# Addon-LAN-WLAN-without-MAPLE-V01-001.net
KiCad netlist of a schematic drawn in EAGLE
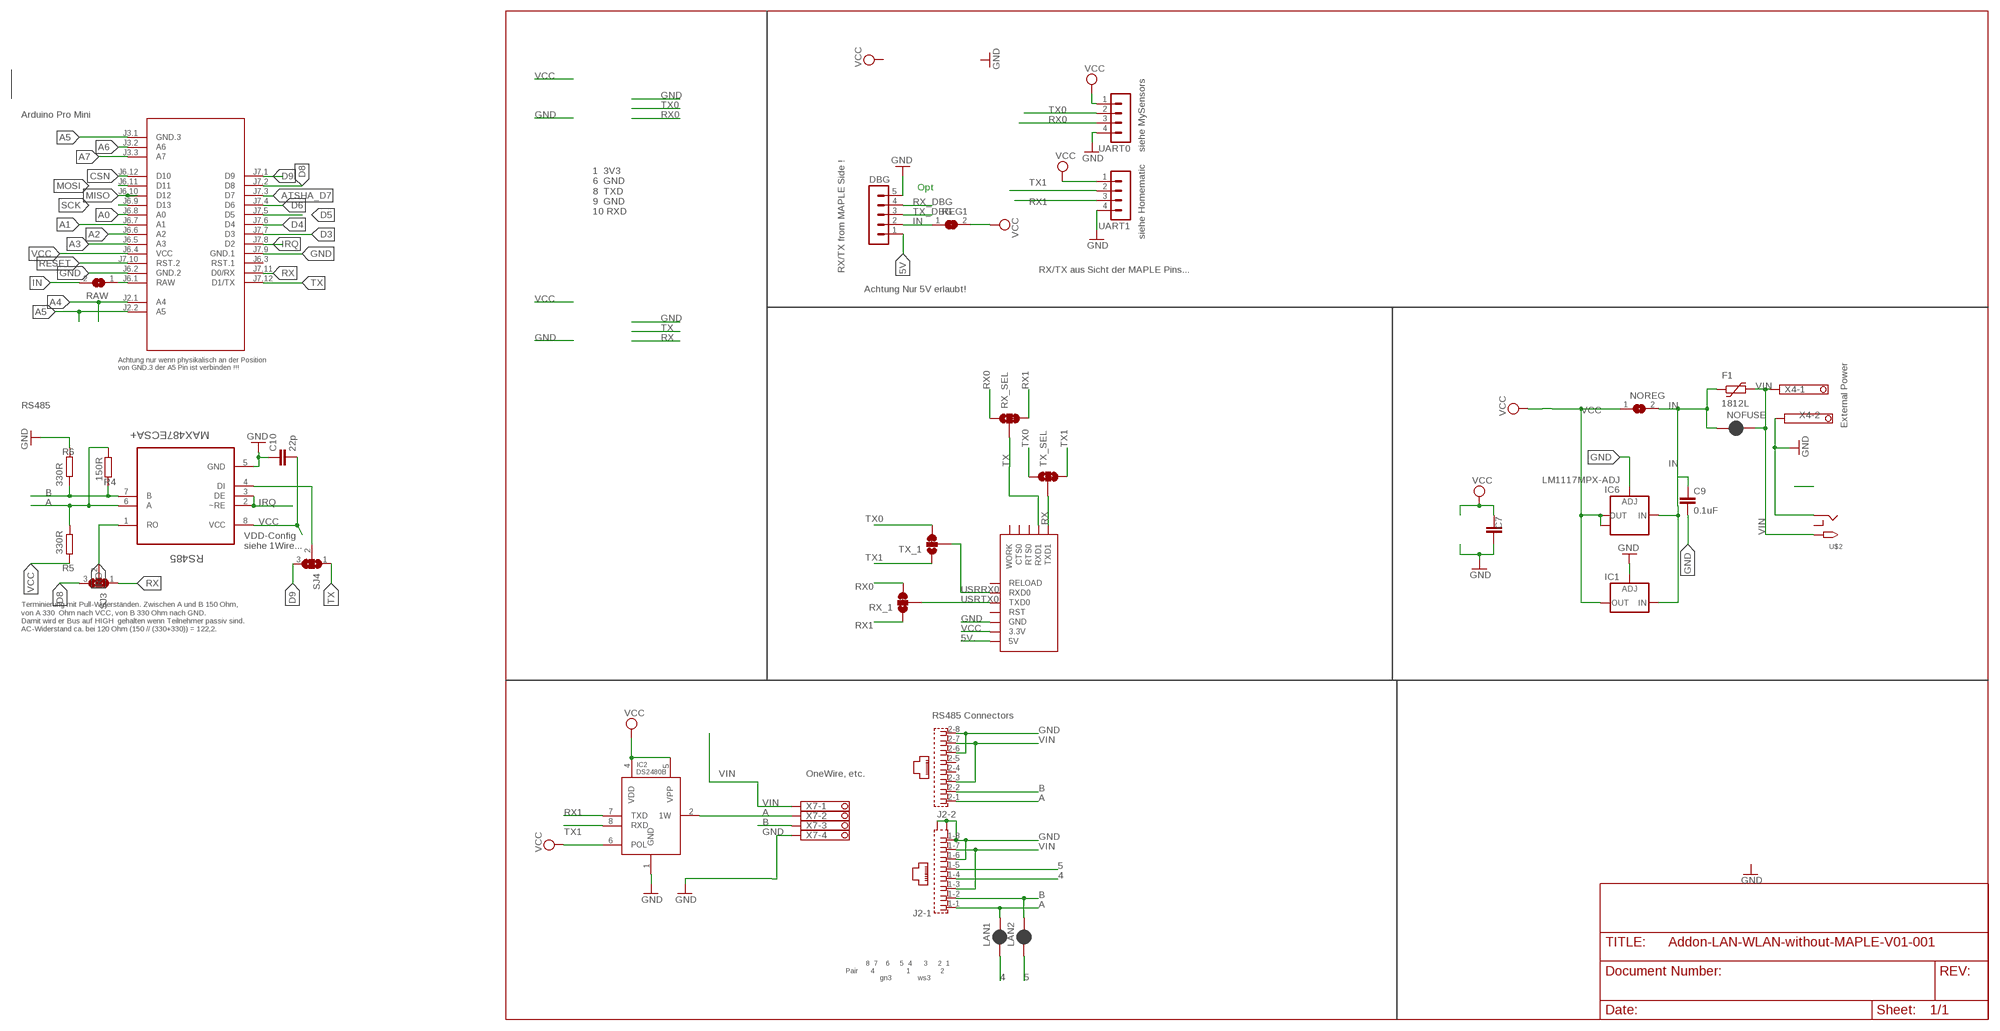
[diagram p0: schematic, sheet 1]

(export (version "E")
  (design (tool "Eeschema 10.0.6"))
  (components
    (comp (ref "C7")
      (value "C-EUC1812")
      (footprint "eagle-import:C1812")
      (libsource (lib "eagle-import") (part "rcl_334_C-EUC1812"))
    )
    (comp (ref "C9")
      (value "0.1uF")
      (footprint "eagle-import:C1206")
      (libsource (lib "eagle-import") (part "rcl_334_C-EUC1206"))
    )
    (comp (ref "C10")
      (value "22p")
      (footprint "eagle-import:C0805")
      (libsource (lib "eagle-import") (part "C-EUC0805"))
    )
    (comp (ref "DBG")
      (value "MA05-1")
      (footprint "eagle-import:MA05-1")
      (libsource (lib "eagle-import") (part "MA05-1"))
    )
    (comp (ref "F1")
      (value "1812L")
      (footprint "eagle-import:1812L")
      (libsource (lib "eagle-import") (part "1812L"))
    )
    (comp (ref "IC1")
      (value "LD117ADT50TR")
      (footprint "eagle-import:DPACK")
      (libsource (lib "eagle-import") (part "LD117A?DT50TR"))
    )
    (comp (ref "IC2")
      (value "DS2480B")
      (footprint "eagle-import:SO08")
      (libsource (lib "eagle-import") (part "DS2480B"))
    )
    (comp (ref "IC6")
      (value "LM1117MPX-ADJ")
      (footprint "eagle-import:SOT223")
      (libsource (lib "eagle-import") (part "LM1117MPX-ADJ"))
    )
    (comp (ref "J2")
      (value "RJ45_2X_S")
      (footprint "eagle-import:RJ45_2X_S")
      (libsource (lib "eagle-import") (part "RJ45_2X_S"))
    )
    (comp (ref "LAN1")
      (value "JUMPER-SMT_2_NC_PASTE_SILK")
      (footprint "eagle-import:SMT-JUMPER_2_NC_PASTE_SILK")
      (libsource (lib "eagle-import") (part "JUMPER-SMT_2_NC_PASTE_SILK"))
    )
    (comp (ref "LAN2")
      (value "JUMPER-SMT_2_NC_PASTE_SILK")
      (footprint "eagle-import:SMT-JUMPER_2_NC_PASTE_SILK")
      (libsource (lib "eagle-import") (part "JUMPER-SMT_2_NC_PASTE_SILK"))
    )
    (comp (ref "M1")
      (value "ARDUINO-PRO-MINI-3.3V#NP")
      (footprint "eagle-import:ARDUINO-PRO-MINI#NP")
      (libsource (lib "eagle-import") (part "ARDUINO-PRO-MINI-#NP3.3V"))
    )
    (comp (ref "NOFUSE")
      (value "JUMPER-SMT_2_NC_PASTE_NO-SILK")
      (footprint "eagle-import:SMT-JUMPER_2_NC_PASTE_NO-SILK")
      (libsource (lib "eagle-import") (part "JUMPER-SMT_2_NC_PASTE_NO-SILK"))
    )
    (comp (ref "NOREG")
      (value "SJ")
      (footprint "eagle-import:SJ")
      (libsource (lib "eagle-import") (part "jumper_252_SJ"))
    )
    (comp (ref "R4")
      (value "150R")
      (footprint "eagle-import:R0805")
      (libsource (lib "eagle-import") (part "R-EU_R0805"))
    )
    (comp (ref "R5")
      (value "330R")
      (footprint "eagle-import:R0805")
      (libsource (lib "eagle-import") (part "R-EU_R0805"))
    )
    (comp (ref "R6")
      (value "330R")
      (footprint "eagle-import:R0805")
      (libsource (lib "eagle-import") (part "R-EU_R0805"))
    )
    (comp (ref "RAW") (value "SJ") (footprint "eagle-import:SJ") (libsource (lib "eagle-import") (part "SJ")))
    (comp (ref "REG1")
      (value "SJ")
      (footprint "eagle-import:SJ")
      (libsource (lib "eagle-import") (part "jumper_252_SJ"))
    )
    (comp (ref "RS485")
      (value "MAX487ECSA+")
      (footprint "eagle-import:SOIC127P600X175-8N")
      (libsource (lib "eagle-import") (part "MAX487ECSA+"))
    )
    (comp (ref "RX_1")
      (value "JUMPER-SMT_3_1-NC_TRACE_SILK")
      (footprint "eagle-import:SMT-JUMPER_3_1-NC_TRACE_SILK")
      (libsource (lib "eagle-import") (part "JUMPER-SMT_3_1-NC_TRACE_SILK"))
    )
    (comp (ref "RX_SEL")
      (value "JUMPER-SMT_3_1-NC_TRACE_SILK")
      (footprint "eagle-import:SMT-JUMPER_3_1-NC_TRACE_SILK")
      (libsource (lib "eagle-import") (part "JUMPER-SMT_3_1-NC_TRACE_SILK"))
    )
    (comp (ref "SJ3")
      (value "SJ2W")
      (footprint "eagle-import:SJ_2")
      (libsource (lib "eagle-import") (part "SJ2W"))
    )
    (comp (ref "SJ4")
      (value "SJ2W")
      (footprint "eagle-import:SJ_2")
      (libsource (lib "eagle-import") (part "SJ2W"))
    )
    (comp (ref "TX_1")
      (value "JUMPER-SMT_3_1-NC_TRACE_SILK")
      (footprint "eagle-import:SMT-JUMPER_3_1-NC_TRACE_SILK")
      (libsource (lib "eagle-import") (part "JUMPER-SMT_3_1-NC_TRACE_SILK"))
    )
    (comp (ref "TX_SEL")
      (value "JUMPER-SMT_3_1-NC_TRACE_SILK")
      (footprint "eagle-import:SMT-JUMPER_3_1-NC_TRACE_SILK")
      (libsource (lib "eagle-import") (part "JUMPER-SMT_3_1-NC_TRACE_SILK"))
    )
    (comp (ref "U$2")
      (value "2.1MMJACKTHM")
      (footprint "eagle-import:PJ-102A")
      (libsource (lib "eagle-import") (part "2.1MMJACKTHM"))
    )
    (comp (ref "U$5")
      (value "USR-TCP232-E2")
      (footprint "eagle-import:USR-TCP232-E2")
      (libsource (lib "eagle-import") (part "USR-TCP232-E2"))
    )
    (comp (ref "UART0")
      (value "MA04-1")
      (footprint "eagle-import:MA04-1")
      (libsource (lib "eagle-import") (part "MA04-1"))
    )
    (comp (ref "UART1")
      (value "MA04-1")
      (footprint "eagle-import:MA04-1")
      (libsource (lib "eagle-import") (part "MA04-1"))
    )
    (comp (ref "X4")
      (value "1751248")
      (footprint "eagle-import:1751248")
      (libsource (lib "eagle-import") (part "1751248"))
    )
    (comp (ref "X7")
      (value "1751264")
      (footprint "eagle-import:1751264")
      (libsource (lib "eagle-import") (part "1751264"))
    )
  )
  (nets
    (net (code "1") (name "/4") (class "Default")
      (node (ref "J2") (pin "1-4") (pinfunction "4_1-4") (pintype "passive"))
      (node (ref "LAN1") (pin "1") (pinfunction "1_1") (pintype "passive"))
    )
    (net (code "2") (name "/5") (class "Default")
      (node (ref "J2") (pin "1-5") (pinfunction "5_1-5") (pintype "passive"))
      (node (ref "LAN2") (pin "1") (pinfunction "1_1") (pintype "passive"))
    )
    (net (code "3") (name "/5V.") (class "Default")
      (node (ref "U$5") (pin "5V") (pinfunction "5V_5V") (pintype "bidirectional"))
    )
    (net (code "4") (name "/A") (class "Default")
      (node (ref "IC2") (pin "2") (pinfunction "1W_2") (pintype "open_collector"))
      (node (ref "J2") (pin "1-1") (pinfunction "1_1-1") (pintype "passive"))
      (node (ref "J2") (pin "2-1") (pinfunction "1_2-1") (pintype "passive"))
      (node (ref "LAN1") (pin "2") (pinfunction "2_2") (pintype "passive"))
      (node (ref "R4") (pin "1") (pinfunction "1_1") (pintype "passive"))
      (node (ref "R5") (pin "2") (pinfunction "2_2") (pintype "passive"))
      (node (ref "RS485") (pin "6") (pinfunction "A_6") (pintype "bidirectional"))
      (node (ref "X7") (pin "2") (pinfunction "K_2") (pintype "passive"))
    )
    (net (code "5") (name "/B") (class "Default")
      (node (ref "J2") (pin "1-2") (pinfunction "2_1-2") (pintype "passive"))
      (node (ref "J2") (pin "2-2") (pinfunction "2_2-2") (pintype "passive"))
      (node (ref "LAN2") (pin "2") (pinfunction "2_2") (pintype "passive"))
      (node (ref "R4") (pin "2") (pinfunction "2_2") (pintype "passive"))
      (node (ref "R6") (pin "1") (pinfunction "1_1") (pintype "passive"))
      (node (ref "RS485") (pin "7") (pinfunction "B_7") (pintype "bidirectional"))
      (node (ref "X7") (pin "3") (pinfunction "K_3") (pintype "passive"))
    )
    (net (code "6") (name "/RX0") (class "Default")
      (node (ref "RX_1") (pin "3") (pinfunction "3_3") (pintype "passive"))
      (node (ref "RX_SEL") (pin "1") (pinfunction "1_1") (pintype "passive"))
      (node (ref "UART0") (pin "3") (pinfunction "3_3") (pintype "passive"))
    )
    (net (code "7") (name "/RX1") (class "Default")
      (node (ref "IC2") (pin "7") (pinfunction "TXD_7") (pintype "input"))
      (node (ref "RX_1") (pin "1") (pinfunction "1_1") (pintype "passive"))
      (node (ref "RX_SEL") (pin "3") (pinfunction "3_3") (pintype "passive"))
      (node (ref "UART1") (pin "3") (pinfunction "3_3") (pintype "passive"))
    )
    (net (code "8") (name "/RX_DBG") (class "Default")
      (node (ref "DBG") (pin "4") (pinfunction "4_4") (pintype "passive"))
    )
    (net (code "9") (name "/TX0") (class "Default")
      (node (ref "TX_1") (pin "3") (pinfunction "3_3") (pintype "passive"))
      (node (ref "TX_SEL") (pin "1") (pinfunction "1_1") (pintype "passive"))
      (node (ref "UART0") (pin "2") (pinfunction "2_2") (pintype "passive"))
    )
    (net (code "10") (name "/TX1") (class "Default")
      (node (ref "IC2") (pin "8") (pinfunction "RXD_8") (pintype "output"))
      (node (ref "TX_1") (pin "1") (pinfunction "1_1") (pintype "passive"))
      (node (ref "TX_SEL") (pin "3") (pinfunction "3_3") (pintype "passive"))
      (node (ref "UART1") (pin "2") (pinfunction "2_2") (pintype "passive"))
    )
    (net (code "11") (name "/TX_DBG") (class "Default")
      (node (ref "DBG") (pin "3") (pinfunction "3_3") (pintype "passive"))
    )
    (net (code "12") (name "/USRRX0") (class "Default")
      (node (ref "TX_1") (pin "2") (pinfunction "2_2") (pintype "passive"))
      (node (ref "U$5") (pin "RXD0") (pinfunction "RXD0_RXD0") (pintype "input"))
    )
    (net (code "13") (name "/USRTX0") (class "Default")
      (node (ref "RX_1") (pin "2") (pinfunction "2_2") (pintype "passive"))
      (node (ref "U$5") (pin "TXD0") (pinfunction "TXD0_TXD0") (pintype "output"))
    )
    (net (code "14") (name "/VIN") (class "Default")
      (node (ref "F1") (pin "P$2") (pinfunction "2_P$2") (pintype "passive"))
      (node (ref "J2") (pin "1-3") (pinfunction "3_1-3") (pintype "passive"))
      (node (ref "J2") (pin "1-7") (pinfunction "7_1-7") (pintype "passive"))
      (node (ref "J2") (pin "2-3") (pinfunction "3_2-3") (pintype "passive"))
      (node (ref "J2") (pin "2-7") (pinfunction "7_2-7") (pintype "passive"))
      (node (ref "NOFUSE") (pin "2") (pinfunction "2_2") (pintype "passive"))
      (node (ref "U$2") (pin "TIP") (pinfunction "TIP_TIP") (pintype "bidirectional"))
      (node (ref "X4") (pin "1") (pinfunction "K_1") (pintype "passive"))
      (node (ref "X7") (pin "1") (pinfunction "K_1") (pintype "passive"))
    )
    (net (code "15") (name "5V") (class "Default")
      (node (ref "DBG") (pin "1") (pinfunction "1_1") (pintype "passive"))
    )
    (net (code "16") (name "A0") (class "Default")
      (node (ref "M1") (pin "J6.8") (pinfunction "A0_J6.8") (pintype "bidirectional"))
    )
    (net (code "17") (name "A1") (class "Default")
      (node (ref "M1") (pin "J6.7") (pinfunction "A1_J6.7") (pintype "bidirectional"))
    )
    (net (code "18") (name "A2") (class "Default")
      (node (ref "M1") (pin "J6.6") (pinfunction "A2_J6.6") (pintype "bidirectional"))
    )
    (net (code "19") (name "A3") (class "Default")
      (node (ref "M1") (pin "J6.5") (pinfunction "A3_J6.5") (pintype "bidirectional"))
    )
    (net (code "20") (name "A4") (class "Default")
      (node (ref "M1") (pin "J2.1") (pinfunction "A4_J2.1") (pintype "bidirectional"))
    )
    (net (code "21") (name "A5") (class "Default")
      (node (ref "M1") (pin "J2.2") (pinfunction "A5_J2.2") (pintype "bidirectional"))
      (node (ref "M1") (pin "J3.1") (pinfunction "GND.3_J3.1") (pintype "bidirectional"))
    )
    (net (code "22") (name "A6") (class "Default")
      (node (ref "M1") (pin "J3.2") (pinfunction "A6_J3.2") (pintype "bidirectional"))
    )
    (net (code "23") (name "A7") (class "Default")
      (node (ref "M1") (pin "J3.3") (pinfunction "A7_J3.3") (pintype "bidirectional"))
    )
    (net (code "24") (name "ATSHA_D7") (class "Default")
      (node (ref "M1") (pin "J7.3") (pinfunction "D7_J7.3") (pintype "bidirectional"))
    )
    (net (code "25") (name "CSN") (class "Default")
      (node (ref "M1") (pin "J6.12") (pinfunction "D10_J6.12") (pintype "bidirectional"))
    )
    (net (code "26") (name "D3") (class "Default")
      (node (ref "M1") (pin "J7.7") (pinfunction "D3_J7.7") (pintype "bidirectional"))
    )
    (net (code "27") (name "D4") (class "Default")
      (node (ref "M1") (pin "J7.6") (pinfunction "D4_J7.6") (pintype "bidirectional"))
    )
    (net (code "28") (name "D5") (class "Default")
      (node (ref "M1") (pin "J7.5") (pinfunction "D5_J7.5") (pintype "bidirectional"))
    )
    (net (code "29") (name "D6") (class "Default")
      (node (ref "M1") (pin "J7.4") (pinfunction "D6_J7.4") (pintype "bidirectional"))
    )
    (net (code "30") (name "D8") (class "Default")
      (node (ref "M1") (pin "J7.2") (pinfunction "D8_J7.2") (pintype "bidirectional"))
      (node (ref "SJ3") (pin "3") (pinfunction "3_3") (pintype "passive"))
    )
    (net (code "31") (name "D9") (class "Default")
      (node (ref "M1") (pin "J7.1") (pinfunction "D9_J7.1") (pintype "bidirectional"))
      (node (ref "SJ4") (pin "3") (pinfunction "3_3") (pintype "passive"))
    )
    (net (code "32") (name "GND") (class "Default")
      (node (ref "C10") (pin "1") (pinfunction "1_1") (pintype "passive"))
      (node (ref "C7") (pin "1") (pinfunction "1_1") (pintype "passive"))
      (node (ref "C9") (pin "2") (pinfunction "2_2") (pintype "passive"))
      (node (ref "DBG") (pin "5") (pinfunction "5_5") (pintype "passive"))
      (node (ref "IC1") (pin "1") (pinfunction "ADJ_1") (pintype "input"))
      (node (ref "IC2") (pin "1") (pinfunction "GND_1") (pintype "power_in"))
      (node (ref "IC6") (pin "1") (pinfunction "ADJ_1") (pintype "input"))
      (node (ref "J2") (pin "1-6") (pinfunction "6_1-6") (pintype "passive"))
      (node (ref "J2") (pin "1-8") (pinfunction "8_1-8") (pintype "passive"))
      (node (ref "J2") (pin "2-6") (pinfunction "6_2-6") (pintype "passive"))
      (node (ref "J2") (pin "2-8") (pinfunction "8_2-8") (pintype "passive"))
      (node (ref "J2") (pin "G1") (pinfunction "S2_G1") (pintype "passive"))
      (node (ref "J2") (pin "G3") (pinfunction "S1_G3") (pintype "passive"))
      (node (ref "M1") (pin "J6.2") (pinfunction "GND.2_J6.2") (pintype "power_in"))
      (node (ref "M1") (pin "J7.9") (pinfunction "GND.1_J7.9") (pintype "power_in"))
      (node (ref "R6") (pin "2") (pinfunction "2_2") (pintype "passive"))
      (node (ref "RS485") (pin "5") (pinfunction "GND_5") (pintype "passive"))
      (node (ref "U$2") (pin "RING") (pinfunction "RING_RING") (pintype "bidirectional"))
      (node (ref "U$5") (pin "GND") (pinfunction "GND_GND") (pintype "bidirectional"))
      (node (ref "UART0") (pin "4") (pinfunction "4_4") (pintype "passive"))
      (node (ref "UART1") (pin "4") (pinfunction "4_4") (pintype "passive"))
      (node (ref "X4") (pin "2") (pinfunction "K_2") (pintype "passive"))
      (node (ref "X7") (pin "4") (pinfunction "K_4") (pintype "passive"))
    )
    (net (code "33") (name "IN") (class "Default")
      (node (ref "C9") (pin "1") (pinfunction "1_1") (pintype "passive"))
      (node (ref "DBG") (pin "2") (pinfunction "2_2") (pintype "passive"))
      (node (ref "F1") (pin "P$1") (pinfunction "1_P$1") (pintype "passive"))
      (node (ref "IC1") (pin "3") (pinfunction "IN_3") (pintype "input"))
      (node (ref "IC6") (pin "3") (pinfunction "IN_3") (pintype "input"))
      (node (ref "NOFUSE") (pin "1") (pinfunction "1_1") (pintype "passive"))
      (node (ref "NOREG") (pin "2") (pinfunction "2_2") (pintype "passive"))
      (node (ref "RAW") (pin "2") (pinfunction "2_2") (pintype "passive"))
      (node (ref "REG1") (pin "1") (pinfunction "1_1") (pintype "passive"))
    )
    (net (code "34") (name "IRQ") (class "Default")
      (node (ref "M1") (pin "J7.8") (pinfunction "D2_J7.8") (pintype "bidirectional"))
      (node (ref "RS485") (pin "2") (pinfunction "~{RE}_2") (pintype "input"))
      (node (ref "RS485") (pin "3") (pinfunction "DE_3") (pintype "input"))
    )
    (net (code "35") (name "MISO") (class "Default")
      (node (ref "M1") (pin "J6.10") (pinfunction "D12_J6.10") (pintype "bidirectional"))
    )
    (net (code "36") (name "MOSI") (class "Default")
      (node (ref "M1") (pin "J6.11") (pinfunction "D11_J6.11") (pintype "bidirectional"))
    )
    (net (code "37") (name "Net-(M1-RAW)") (class "Default")
      (node (ref "M1") (pin "J6.1") (pinfunction "RAW_J6.1") (pintype "power_in"))
      (node (ref "RAW") (pin "1") (pinfunction "1_1") (pintype "passive"))
    )
    (net (code "38") (name "Net-(RS485-DI)") (class "Default")
      (node (ref "RS485") (pin "4") (pinfunction "DI_4") (pintype "input"))
      (node (ref "SJ4") (pin "2") (pinfunction "2_2") (pintype "passive"))
    )
    (net (code "39") (name "RESET") (class "Default")
      (node (ref "M1") (pin "J7.10") (pinfunction "RST.2_J7.10") (pintype "bidirectional"))
    )
    (net (code "40") (name "RO") (class "Default")
      (node (ref "RS485") (pin "1") (pinfunction "RO_1") (pintype "output"))
      (node (ref "SJ3") (pin "2") (pinfunction "2_2") (pintype "passive"))
    )
    (net (code "41") (name "RX") (class "Default")
      (node (ref "M1") (pin "J7.11") (pinfunction "D0/RX_J7.11") (pintype "bidirectional"))
      (node (ref "SJ3") (pin "1") (pinfunction "1_1") (pintype "passive"))
      (node (ref "TX_SEL") (pin "2") (pinfunction "2_2") (pintype "passive"))
      (node (ref "U$5") (pin "TXD1") (pinfunction "TXD1_TXD1") (pintype "output"))
    )
    (net (code "42") (name "SCK") (class "Default")
      (node (ref "M1") (pin "J6.9") (pinfunction "D13_J6.9") (pintype "bidirectional"))
    )
    (net (code "43") (name "TX") (class "Default")
      (node (ref "M1") (pin "J7.12") (pinfunction "D1/TX_J7.12") (pintype "bidirectional"))
      (node (ref "RX_SEL") (pin "2") (pinfunction "2_2") (pintype "passive"))
      (node (ref "SJ4") (pin "1") (pinfunction "1_1") (pintype "passive"))
      (node (ref "U$5") (pin "RXD1") (pinfunction "RXD1_RXD1") (pintype "input"))
    )
    (net (code "44") (name "VCC") (class "Default")
      (node (ref "C10") (pin "2") (pinfunction "2_2") (pintype "passive"))
      (node (ref "C7") (pin "2") (pinfunction "2_2") (pintype "passive"))
      (node (ref "IC1") (pin "4") (pinfunction "OUT_4") (pintype "passive"))
      (node (ref "IC2") (pin "4") (pinfunction "VDD_4") (pintype "power_in"))
      (node (ref "IC2") (pin "5") (pinfunction "VPP_5") (pintype "power_in"))
      (node (ref "IC2") (pin "6") (pinfunction "POL_6") (pintype "input"))
      (node (ref "IC6") (pin "2") (pinfunction "OUT_2") (pintype "passive"))
      (node (ref "IC6") (pin "TAB") (pinfunction "OUT1_TAB") (pintype "passive"))
      (node (ref "M1") (pin "J6.4") (pinfunction "VCC_J6.4") (pintype "power_in"))
      (node (ref "NOREG") (pin "1") (pinfunction "1_1") (pintype "passive"))
      (node (ref "R5") (pin "1") (pinfunction "1_1") (pintype "passive"))
      (node (ref "REG1") (pin "2") (pinfunction "2_2") (pintype "passive"))
      (node (ref "RS485") (pin "8") (pinfunction "VCC_8") (pintype "power_in"))
      (node (ref "U$5") (pin "3.3V") (pinfunction "3.3V_3.3V") (pintype "bidirectional"))
      (node (ref "UART0") (pin "1") (pinfunction "1_1") (pintype "passive"))
      (node (ref "UART1") (pin "1") (pinfunction "1_1") (pintype "passive"))
    )
    (net (code "45") (name "unconnected-(J2B-4-Pad2-4)") (class "Default")
      (node (ref "J2") (pin "2-4") (pinfunction "4_2-4") (pintype "passive"))
    )
    (net (code "46") (name "unconnected-(J2B-5-Pad2-5)") (class "Default")
      (node (ref "J2") (pin "2-5") (pinfunction "5_2-5") (pintype "passive"))
    )
    (net (code "47") (name "unconnected-(M1-RST.1-PadJ6.3)") (class "Default")
      (node (ref "M1") (pin "J6.3") (pinfunction "RST.1_J6.3") (pintype "bidirectional"))
    )
    (net (code "48") (name "unconnected-(U$2-PadRING_SW)") (class "Default")
      (node (ref "U$2") (pin "RING_SW") (pinfunction "RING_SW_RING_SW") (pintype "bidirectional"))
    )
    (net (code "49") (name "unconnected-(U$5-PadCTS0)") (class "Default")
      (node (ref "U$5") (pin "CTS0") (pinfunction "CTS0_CTS0") (pintype "bidirectional"))
    )
    (net (code "50") (name "unconnected-(U$5-PadRELOAD)") (class "Default")
      (node (ref "U$5") (pin "RELOAD") (pinfunction "RELOAD_RELOAD") (pintype "bidirectional"))
    )
    (net (code "51") (name "unconnected-(U$5-PadRST)") (class "Default")
      (node (ref "U$5") (pin "RST") (pinfunction "RST_RST") (pintype "bidirectional"))
    )
    (net (code "52") (name "unconnected-(U$5-PadRTS0)") (class "Default")
      (node (ref "U$5") (pin "RTS0") (pinfunction "RTS0_RTS0") (pintype "bidirectional"))
    )
    (net (code "53") (name "unconnected-(U$5-PadWORK)") (class "Default")
      (node (ref "U$5") (pin "WORK") (pinfunction "WORK_WORK") (pintype "bidirectional"))
    )
  )
)
